# OGX360I-4CH_-_Main.net
KiCad netlist of a schematic drawn in EAGLE
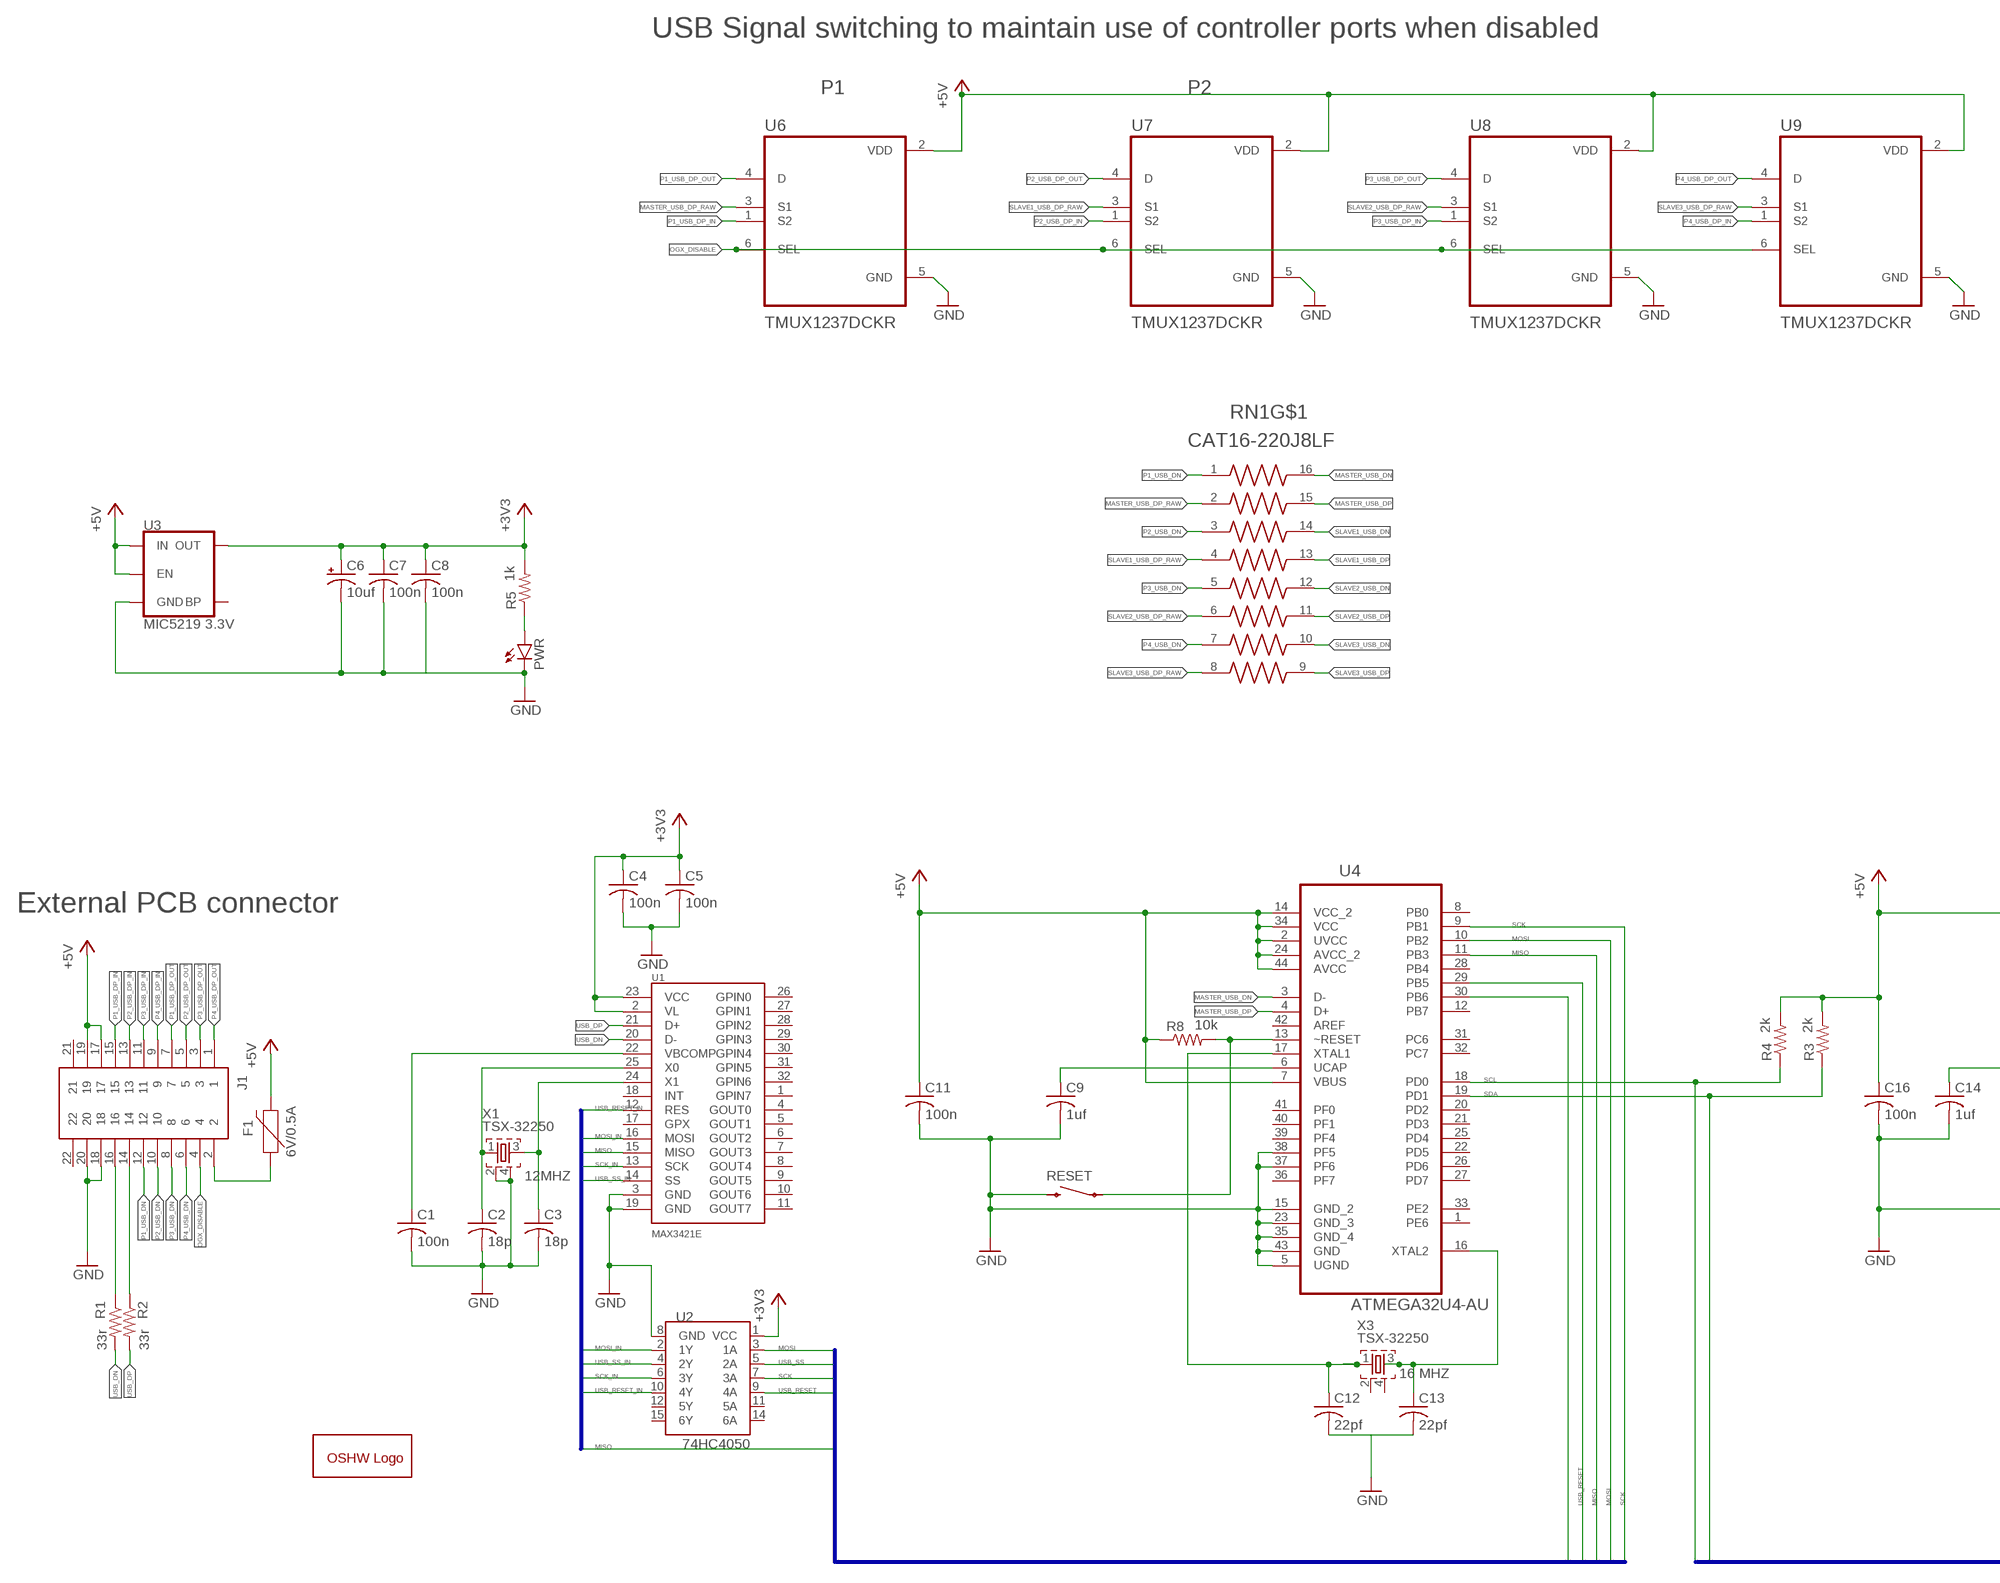
[diagram p0: schematic, sheet 1, part 1 of 2]
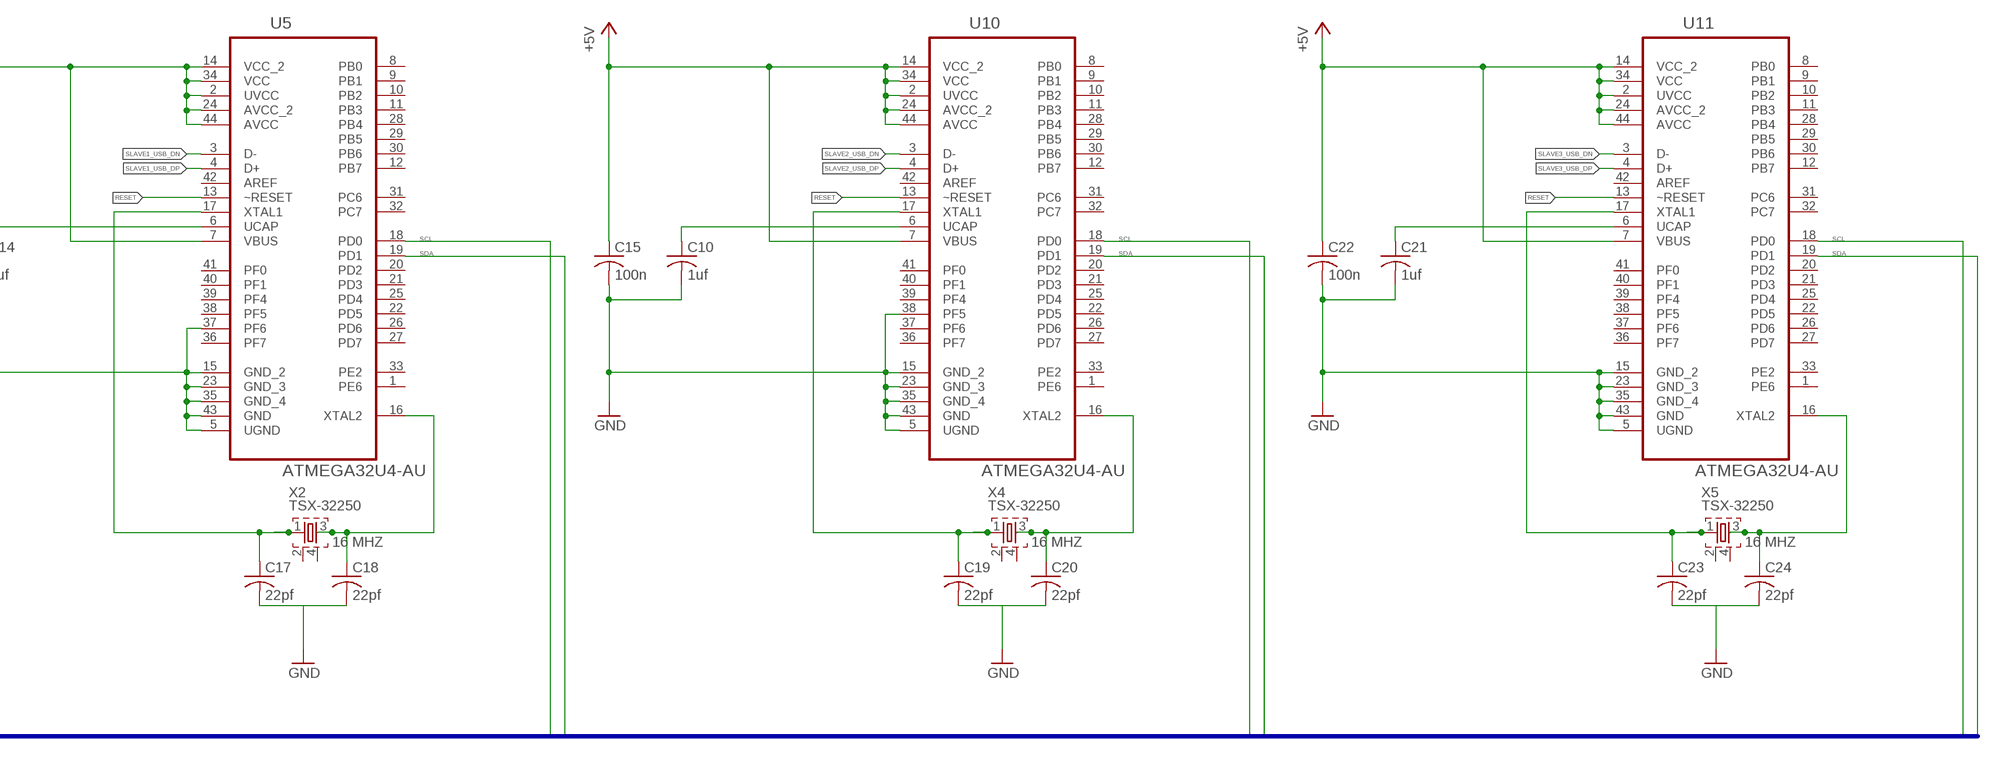
[diagram p1: schematic, sheet 1, part 2 of 2]

(export (version "E")
  (design (tool "Eeschema 10.0.6"))
  (components
    (comp (ref "C1")
      (value "100n")
      (footprint "eagle-import:C0805")
      (libsource (lib "eagle-import") (part "C-USC0805"))
    )
    (comp (ref "C2")
      (value "18p")
      (footprint "eagle-import:C0805")
      (libsource (lib "eagle-import") (part "C-USC0805"))
    )
    (comp (ref "C3")
      (value "18p")
      (footprint "eagle-import:C0805")
      (libsource (lib "eagle-import") (part "C-USC0805"))
    )
    (comp (ref "C4")
      (value "100n")
      (footprint "eagle-import:C0805")
      (libsource (lib "eagle-import") (part "C-USC0805"))
    )
    (comp (ref "C5")
      (value "100n")
      (footprint "eagle-import:C0805")
      (libsource (lib "eagle-import") (part "C-USC0805"))
    )
    (comp (ref "C6")
      (value "10uf")
      (footprint "eagle-import:153CLV-0405")
      (libsource (lib "eagle-import") (part "CPOL-US153CLV-0405"))
    )
    (comp (ref "C7")
      (value "100n")
      (footprint "eagle-import:C0805")
      (libsource (lib "eagle-import") (part "C-USC0805"))
    )
    (comp (ref "C8")
      (value "100n")
      (footprint "eagle-import:C0805")
      (libsource (lib "eagle-import") (part "C-USC0805"))
    )
    (comp (ref "C9")
      (value "1uf")
      (footprint "eagle-import:C0805")
      (libsource (lib "eagle-import") (part "C-USC0805"))
    )
    (comp (ref "C10")
      (value "1uf")
      (footprint "eagle-import:C0805")
      (libsource (lib "eagle-import") (part "C-USC0805"))
    )
    (comp (ref "C11")
      (value "100n")
      (footprint "eagle-import:C0805")
      (libsource (lib "eagle-import") (part "C-USC0805"))
    )
    (comp (ref "C12")
      (value "22pf")
      (footprint "eagle-import:C0805")
      (libsource (lib "eagle-import") (part "C-USC0805"))
    )
    (comp (ref "C13")
      (value "22pf")
      (footprint "eagle-import:C0805")
      (libsource (lib "eagle-import") (part "C-USC0805"))
    )
    (comp (ref "C14")
      (value "1uf")
      (footprint "eagle-import:C0805")
      (libsource (lib "eagle-import") (part "C-USC0805"))
    )
    (comp (ref "C15")
      (value "100n")
      (footprint "eagle-import:C0805")
      (libsource (lib "eagle-import") (part "C-USC0805"))
    )
    (comp (ref "C16")
      (value "100n")
      (footprint "eagle-import:C0805")
      (libsource (lib "eagle-import") (part "C-USC0805"))
    )
    (comp (ref "C17")
      (value "22pf")
      (footprint "eagle-import:C0805")
      (libsource (lib "eagle-import") (part "C-USC0805"))
    )
    (comp (ref "C18")
      (value "22pf")
      (footprint "eagle-import:C0805")
      (libsource (lib "eagle-import") (part "C-USC0805"))
    )
    (comp (ref "C19")
      (value "22pf")
      (footprint "eagle-import:C0805")
      (libsource (lib "eagle-import") (part "C-USC0805"))
    )
    (comp (ref "C20")
      (value "22pf")
      (footprint "eagle-import:C0805")
      (libsource (lib "eagle-import") (part "C-USC0805"))
    )
    (comp (ref "C21")
      (value "1uf")
      (footprint "eagle-import:C0805")
      (libsource (lib "eagle-import") (part "C-USC0805"))
    )
    (comp (ref "C22")
      (value "100n")
      (footprint "eagle-import:C0805")
      (libsource (lib "eagle-import") (part "C-USC0805"))
    )
    (comp (ref "C23")
      (value "22pf")
      (footprint "eagle-import:C0805")
      (libsource (lib "eagle-import") (part "C-USC0805"))
    )
    (comp (ref "C24")
      (value "22pf")
      (footprint "eagle-import:C0805")
      (libsource (lib "eagle-import") (part "C-USC0805"))
    )
    (comp (ref "F1")
      (value "6V/0.5A")
      (footprint "eagle-import:1206")
      (libsource (lib "eagle-import") (part "PPTC_HALF-AMP"))
    )
    (comp (ref "GOLD_ORB_SM1")
      (value "OSHWLOGOLOGO8MM")
      (footprint "eagle-import:OSHW_8MM")
      (libsource (lib "eagle-import") (part "OSHWLOGOLOGO8MM"))
    )
    (comp (ref "J1")
      (value "SM20B-SRDS-G-TF(LF)(SN)")
      (footprint "eagle-import:SM20BSRDSGTFLFSN")
      (libsource (lib "eagle-import") (part "SM20B-SRDS-G-TF(LF)(SN)"))
    )
    (comp (ref "PWR")
      (value "LEDCHIP-LED0805")
      (footprint "eagle-import:CHIP-LED0805")
      (libsource (lib "eagle-import") (part "LEDCHIP-LED0805"))
    )
    (comp (ref "R1")
      (value "33r")
      (footprint "eagle-import:M0805")
      (libsource (lib "eagle-import") (part "R-US_M0805"))
    )
    (comp (ref "R2")
      (value "33r")
      (footprint "eagle-import:M0805")
      (libsource (lib "eagle-import") (part "R-US_M0805"))
    )
    (comp (ref "R3")
      (value "2k")
      (footprint "eagle-import:M0805")
      (libsource (lib "eagle-import") (part "R-US_M0805"))
    )
    (comp (ref "R4")
      (value "2k")
      (footprint "eagle-import:M0805")
      (libsource (lib "eagle-import") (part "R-US_M0805"))
    )
    (comp (ref "R5")
      (value "1k")
      (footprint "eagle-import:M0805")
      (libsource (lib "eagle-import") (part "R-US_M0805"))
    )
    (comp (ref "R8")
      (value "10k")
      (footprint "eagle-import:M0805")
      (libsource (lib "eagle-import") (part "R-US_M0805"))
    )
    (comp (ref "RESET")
      (value "TL3305AF160QG")
      (footprint "eagle-import:TL3305AF160QG")
      (libsource (lib "eagle-import") (part "TL3305AF160QG"))
    )
    (comp (ref "RN1")
      (value "CAT16-220J8LF")
      (footprint "eagle-import:RESCAV80P640X160X75-16N")
      (fields (field (name "MF") "Bourns") (field (name "MP") "CAT16-330J8LF"))
      (libsource (lib "eagle-import") (part "CAT16-330J8LF"))
    )
    (comp (ref "U1")
      (value "MAX3421E")
      (footprint "eagle-import:TQFP32-5MM")
      (fields (field (name "MF") "Maxim Integrated"))
      (libsource (lib "eagle-import") (part "MAX3421E"))
    )
    (comp (ref "U2")
      (value "74HC4050")
      (footprint "eagle-import:SO16")
      (libsource (lib "eagle-import") (part "HEX_CONVERTER"))
    )
    (comp (ref "U3")
      (value "MIC5219 3.3V")
      (footprint "eagle-import:SOT23-5")
      (libsource (lib "eagle-import") (part "V_REG_MIC52193.3V"))
    )
    (comp (ref "U4")
      (value "ATMEGA32U4-AU")
      (footprint "eagle-import:QFP80P1200X1200X120-44N")
      (fields (field (name "MF") "Microchip"))
      (libsource (lib "eagle-import") (part "ATMEGA32U4-AU"))
    )
    (comp (ref "U5")
      (value "ATMEGA32U4-AU")
      (footprint "eagle-import:QFP80P1200X1200X120-44N")
      (fields (field (name "MF") "Microchip"))
      (libsource (lib "eagle-import") (part "ATMEGA32U4-AU"))
    )
    (comp (ref "U6")
      (value "TMUX1237DCKR")
      (footprint "eagle-import:SOT65P210X110-6N")
      (fields (field (name "MF") "Texas Instruments"))
      (libsource (lib "eagle-import") (part "TMUX1237DCKR"))
    )
    (comp (ref "U7")
      (value "TMUX1237DCKR")
      (footprint "eagle-import:SOT65P210X110-6N")
      (fields (field (name "MF") "Texas Instruments"))
      (libsource (lib "eagle-import") (part "TMUX1237DCKR"))
    )
    (comp (ref "U8")
      (value "TMUX1237DCKR")
      (footprint "eagle-import:SOT65P210X110-6N")
      (fields (field (name "MF") "Texas Instruments"))
      (libsource (lib "eagle-import") (part "TMUX1237DCKR"))
    )
    (comp (ref "U9")
      (value "TMUX1237DCKR")
      (footprint "eagle-import:SOT65P210X110-6N")
      (fields (field (name "MF") "Texas Instruments"))
      (libsource (lib "eagle-import") (part "TMUX1237DCKR"))
    )
    (comp (ref "U10")
      (value "ATMEGA32U4-AU")
      (footprint "eagle-import:QFP80P1200X1200X120-44N")
      (fields (field (name "MF") "Microchip"))
      (libsource (lib "eagle-import") (part "ATMEGA32U4-AU"))
    )
    (comp (ref "U11")
      (value "ATMEGA32U4-AU")
      (footprint "eagle-import:QFP80P1200X1200X120-44N")
      (fields (field (name "MF") "Microchip"))
      (libsource (lib "eagle-import") (part "ATMEGA32U4-AU"))
    )
    (comp (ref "X1")
      (value "TSX-32250")
      (footprint "eagle-import:TSX-3225")
      (fields
        (field (name "DIGI-KEY_PART_NUMBER") "SER4180CT-ND")
        (field (name "MF") "EPSON")
        (field (name "MP") "TSX-3225")
      )
      (libsource (lib "eagle-import") (part "TSX-32250"))
    )
    (comp (ref "X2")
      (value "TSX-32250")
      (footprint "eagle-import:TSX-3225")
      (fields
        (field (name "DIGI-KEY_PART_NUMBER") "SER4180CT-ND")
        (field (name "MF") "EPSON")
        (field (name "MP") "TSX-3225")
      )
      (libsource (lib "eagle-import") (part "TSX-32250"))
    )
    (comp (ref "X3")
      (value "TSX-32250")
      (footprint "eagle-import:TSX-3225")
      (fields
        (field (name "DIGI-KEY_PART_NUMBER") "SER4180CT-ND")
        (field (name "MF") "EPSON")
        (field (name "MP") "TSX-3225")
      )
      (libsource (lib "eagle-import") (part "TSX-32250"))
    )
    (comp (ref "X4")
      (value "TSX-32250")
      (footprint "eagle-import:TSX-3225")
      (fields
        (field (name "DIGI-KEY_PART_NUMBER") "SER4180CT-ND")
        (field (name "MF") "EPSON")
        (field (name "MP") "TSX-3225")
      )
      (libsource (lib "eagle-import") (part "TSX-32250"))
    )
    (comp (ref "X5")
      (value "TSX-32250")
      (footprint "eagle-import:TSX-3225")
      (fields
        (field (name "DIGI-KEY_PART_NUMBER") "SER4180CT-ND")
        (field (name "MF") "EPSON")
        (field (name "MP") "TSX-3225")
      )
      (libsource (lib "eagle-import") (part "TSX-32250"))
    )
  )
  (nets
    (net (code "1") (name "+3V3") (class "Default")
      (node (ref "C4") (pin "1") (pinfunction "1_1") (pintype "passive"))
      (node (ref "C5") (pin "1") (pinfunction "1_1") (pintype "passive"))
      (node (ref "C6") (pin "+") (pinfunction "+_+") (pintype "passive"))
      (node (ref "C7") (pin "1") (pinfunction "1_1") (pintype "passive"))
      (node (ref "C8") (pin "1") (pinfunction "1_1") (pintype "passive"))
      (node (ref "R5") (pin "2") (pinfunction "2_2") (pintype "passive"))
      (node (ref "U1") (pin "2") (pinfunction "VL_2") (pintype "bidirectional"))
      (node (ref "U1") (pin "23") (pinfunction "VCC_23") (pintype "bidirectional"))
      (node (ref "U2") (pin "1") (pinfunction "VCC_1") (pintype "bidirectional"))
      (node (ref "U3") (pin "5") (pinfunction "OUT_5") (pintype "passive"))
    )
    (net (code "2") (name "+5V") (class "Default")
      (node (ref "C11") (pin "1") (pinfunction "1_1") (pintype "passive"))
      (node (ref "C15") (pin "1") (pinfunction "1_1") (pintype "passive"))
      (node (ref "C16") (pin "1") (pinfunction "1_1") (pintype "passive"))
      (node (ref "C22") (pin "1") (pinfunction "1_1") (pintype "passive"))
      (node (ref "F1") (pin "2") (pinfunction "2_2") (pintype "bidirectional"))
      (node (ref "J1") (pin "17") (pinfunction "17_17") (pintype "bidirectional"))
      (node (ref "J1") (pin "19") (pinfunction "19_19") (pintype "bidirectional"))
      (node (ref "R3") (pin "2") (pinfunction "2_2") (pintype "passive"))
      (node (ref "R4") (pin "2") (pinfunction "2_2") (pintype "passive"))
      (node (ref "R8") (pin "1") (pinfunction "1_1") (pintype "passive"))
      (node (ref "U10") (pin "14") (pinfunction "VCC_2_14") (pintype "power_in"))
      (node (ref "U10") (pin "2") (pinfunction "UVCC_2") (pintype "power_in"))
      (node (ref "U10") (pin "24") (pinfunction "AVCC_2_24") (pintype "power_in"))
      (node (ref "U10") (pin "34") (pinfunction "VCC_34") (pintype "power_in"))
      (node (ref "U10") (pin "44") (pinfunction "AVCC_44") (pintype "power_in"))
      (node (ref "U10") (pin "7") (pinfunction "VBUS_7") (pintype "input"))
      (node (ref "U11") (pin "14") (pinfunction "VCC_2_14") (pintype "power_in"))
      (node (ref "U11") (pin "2") (pinfunction "UVCC_2") (pintype "power_in"))
      (node (ref "U11") (pin "24") (pinfunction "AVCC_2_24") (pintype "power_in"))
      (node (ref "U11") (pin "34") (pinfunction "VCC_34") (pintype "power_in"))
      (node (ref "U11") (pin "44") (pinfunction "AVCC_44") (pintype "power_in"))
      (node (ref "U11") (pin "7") (pinfunction "VBUS_7") (pintype "input"))
      (node (ref "U3") (pin "1") (pinfunction "IN_1") (pintype "input"))
      (node (ref "U3") (pin "3") (pinfunction "EN_3") (pintype "input"))
      (node (ref "U4") (pin "14") (pinfunction "VCC_2_14") (pintype "power_in"))
      (node (ref "U4") (pin "2") (pinfunction "UVCC_2") (pintype "power_in"))
      (node (ref "U4") (pin "24") (pinfunction "AVCC_2_24") (pintype "power_in"))
      (node (ref "U4") (pin "34") (pinfunction "VCC_34") (pintype "power_in"))
      (node (ref "U4") (pin "44") (pinfunction "AVCC_44") (pintype "power_in"))
      (node (ref "U4") (pin "7") (pinfunction "VBUS_7") (pintype "input"))
      (node (ref "U5") (pin "14") (pinfunction "VCC_2_14") (pintype "power_in"))
      (node (ref "U5") (pin "2") (pinfunction "UVCC_2") (pintype "power_in"))
      (node (ref "U5") (pin "24") (pinfunction "AVCC_2_24") (pintype "power_in"))
      (node (ref "U5") (pin "34") (pinfunction "VCC_34") (pintype "power_in"))
      (node (ref "U5") (pin "44") (pinfunction "AVCC_44") (pintype "power_in"))
      (node (ref "U5") (pin "7") (pinfunction "VBUS_7") (pintype "input"))
      (node (ref "U6") (pin "2") (pinfunction "VDD_2") (pintype "power_in"))
      (node (ref "U7") (pin "2") (pinfunction "VDD_2") (pintype "power_in"))
      (node (ref "U8") (pin "2") (pinfunction "VDD_2") (pintype "power_in"))
      (node (ref "U9") (pin "2") (pinfunction "VDD_2") (pintype "power_in"))
    )
    (net (code "3") (name "/MISO") (class "Default")
      (node (ref "U1") (pin "15") (pinfunction "MISO_15") (pintype "bidirectional"))
      (node (ref "U4") (pin "11") (pinfunction "PB3_11") (pintype "bidirectional"))
    )
    (net (code "4") (name "/MOSI") (class "Default")
      (node (ref "U2") (pin "3") (pinfunction "1A_3") (pintype "bidirectional"))
      (node (ref "U4") (pin "10") (pinfunction "PB2_10") (pintype "bidirectional"))
    )
    (net (code "5") (name "/MOSI_IN") (class "Default")
      (node (ref "U1") (pin "16") (pinfunction "MOSI_16") (pintype "bidirectional"))
      (node (ref "U2") (pin "2") (pinfunction "1Y_2") (pintype "bidirectional"))
    )
    (net (code "6") (name "/SCK") (class "Default")
      (node (ref "U2") (pin "7") (pinfunction "3A_7") (pintype "bidirectional"))
      (node (ref "U4") (pin "9") (pinfunction "PB1_9") (pintype "bidirectional"))
    )
    (net (code "7") (name "/SCK_IN") (class "Default")
      (node (ref "U1") (pin "13") (pinfunction "SCK_13") (pintype "bidirectional"))
      (node (ref "U2") (pin "6") (pinfunction "3Y_6") (pintype "bidirectional"))
    )
    (net (code "8") (name "/SCL") (class "Default")
      (node (ref "R4") (pin "1") (pinfunction "1_1") (pintype "passive"))
      (node (ref "U10") (pin "18") (pinfunction "PD0_18") (pintype "bidirectional"))
      (node (ref "U11") (pin "18") (pinfunction "PD0_18") (pintype "bidirectional"))
      (node (ref "U4") (pin "18") (pinfunction "PD0_18") (pintype "bidirectional"))
      (node (ref "U5") (pin "18") (pinfunction "PD0_18") (pintype "bidirectional"))
    )
    (net (code "9") (name "/SDA") (class "Default")
      (node (ref "R3") (pin "1") (pinfunction "1_1") (pintype "passive"))
      (node (ref "U10") (pin "19") (pinfunction "PD1_19") (pintype "bidirectional"))
      (node (ref "U11") (pin "19") (pinfunction "PD1_19") (pintype "bidirectional"))
      (node (ref "U4") (pin "19") (pinfunction "PD1_19") (pintype "bidirectional"))
      (node (ref "U5") (pin "19") (pinfunction "PD1_19") (pintype "bidirectional"))
    )
    (net (code "10") (name "/USB_RESET") (class "Default")
      (node (ref "U2") (pin "9") (pinfunction "4A_9") (pintype "bidirectional"))
      (node (ref "U4") (pin "29") (pinfunction "PB5_29") (pintype "bidirectional"))
    )
    (net (code "11") (name "/USB_RESET_IN") (class "Default")
      (node (ref "U1") (pin "12") (pinfunction "RES_12") (pintype "bidirectional"))
      (node (ref "U2") (pin "10") (pinfunction "4Y_10") (pintype "bidirectional"))
    )
    (net (code "12") (name "/USB_SS") (class "Default")
      (node (ref "U2") (pin "5") (pinfunction "2A_5") (pintype "bidirectional"))
      (node (ref "U4") (pin "30") (pinfunction "PB6_30") (pintype "bidirectional"))
    )
    (net (code "13") (name "/USB_SS_IN") (class "Default")
      (node (ref "U1") (pin "14") (pinfunction "SS_14") (pintype "bidirectional"))
      (node (ref "U2") (pin "4") (pinfunction "2Y_4") (pintype "bidirectional"))
    )
    (net (code "14") (name "GND") (class "Default")
      (node (ref "C1") (pin "2") (pinfunction "2_2") (pintype "passive"))
      (node (ref "C10") (pin "2") (pinfunction "2_2") (pintype "passive"))
      (node (ref "C11") (pin "2") (pinfunction "2_2") (pintype "passive"))
      (node (ref "C12") (pin "2") (pinfunction "2_2") (pintype "passive"))
      (node (ref "C13") (pin "2") (pinfunction "2_2") (pintype "passive"))
      (node (ref "C14") (pin "2") (pinfunction "2_2") (pintype "passive"))
      (node (ref "C15") (pin "2") (pinfunction "2_2") (pintype "passive"))
      (node (ref "C16") (pin "2") (pinfunction "2_2") (pintype "passive"))
      (node (ref "C17") (pin "2") (pinfunction "2_2") (pintype "passive"))
      (node (ref "C18") (pin "2") (pinfunction "2_2") (pintype "passive"))
      (node (ref "C19") (pin "2") (pinfunction "2_2") (pintype "passive"))
      (node (ref "C2") (pin "2") (pinfunction "2_2") (pintype "passive"))
      (node (ref "C20") (pin "2") (pinfunction "2_2") (pintype "passive"))
      (node (ref "C21") (pin "2") (pinfunction "2_2") (pintype "passive"))
      (node (ref "C22") (pin "2") (pinfunction "2_2") (pintype "passive"))
      (node (ref "C23") (pin "2") (pinfunction "2_2") (pintype "passive"))
      (node (ref "C24") (pin "2") (pinfunction "2_2") (pintype "passive"))
      (node (ref "C3") (pin "2") (pinfunction "2_2") (pintype "passive"))
      (node (ref "C4") (pin "2") (pinfunction "2_2") (pintype "passive"))
      (node (ref "C5") (pin "2") (pinfunction "2_2") (pintype "passive"))
      (node (ref "C6") (pin "-") (pinfunction "-_-") (pintype "passive"))
      (node (ref "C7") (pin "2") (pinfunction "2_2") (pintype "passive"))
      (node (ref "C8") (pin "2") (pinfunction "2_2") (pintype "passive"))
      (node (ref "C9") (pin "2") (pinfunction "2_2") (pintype "passive"))
      (node (ref "J1") (pin "18") (pinfunction "18_18") (pintype "bidirectional"))
      (node (ref "J1") (pin "20") (pinfunction "20_20") (pintype "bidirectional"))
      (node (ref "PWR") (pin "C") (pinfunction "C_C") (pintype "passive"))
      (node (ref "RESET") (pin "P$1") (pinfunction "P$1_P$1") (pintype "bidirectional"))
      (node (ref "RESET") (pin "P$2") (pinfunction "P$1_P$2") (pintype "bidirectional"))
      (node (ref "U1") (pin "19") (pinfunction "GND_19") (pintype "bidirectional"))
      (node (ref "U1") (pin "3") (pinfunction "GND_3") (pintype "bidirectional"))
      (node (ref "U10") (pin "15") (pinfunction "GND_2_15") (pintype "passive"))
      (node (ref "U10") (pin "23") (pinfunction "GND_3_23") (pintype "passive"))
      (node (ref "U10") (pin "35") (pinfunction "GND_4_35") (pintype "passive"))
      (node (ref "U10") (pin "38") (pinfunction "PF5_38") (pintype "bidirectional"))
      (node (ref "U10") (pin "43") (pinfunction "GND_43") (pintype "passive"))
      (node (ref "U10") (pin "5") (pinfunction "UGND_5") (pintype "passive"))
      (node (ref "U11") (pin "15") (pinfunction "GND_2_15") (pintype "passive"))
      (node (ref "U11") (pin "23") (pinfunction "GND_3_23") (pintype "passive"))
      (node (ref "U11") (pin "35") (pinfunction "GND_4_35") (pintype "passive"))
      (node (ref "U11") (pin "43") (pinfunction "GND_43") (pintype "passive"))
      (node (ref "U11") (pin "5") (pinfunction "UGND_5") (pintype "passive"))
      (node (ref "U2") (pin "8") (pinfunction "GND_8") (pintype "bidirectional"))
      (node (ref "U3") (pin "2") (pinfunction "GND_2") (pintype "input"))
      (node (ref "U4") (pin "15") (pinfunction "GND_2_15") (pintype "passive"))
      (node (ref "U4") (pin "23") (pinfunction "GND_3_23") (pintype "passive"))
      (node (ref "U4") (pin "35") (pinfunction "GND_4_35") (pintype "passive"))
      (node (ref "U4") (pin "37") (pinfunction "PF6_37") (pintype "bidirectional"))
      (node (ref "U4") (pin "38") (pinfunction "PF5_38") (pintype "bidirectional"))
      (node (ref "U4") (pin "43") (pinfunction "GND_43") (pintype "passive"))
      (node (ref "U4") (pin "5") (pinfunction "UGND_5") (pintype "passive"))
      (node (ref "U5") (pin "15") (pinfunction "GND_2_15") (pintype "passive"))
      (node (ref "U5") (pin "23") (pinfunction "GND_3_23") (pintype "passive"))
      (node (ref "U5") (pin "35") (pinfunction "GND_4_35") (pintype "passive"))
      (node (ref "U5") (pin "37") (pinfunction "PF6_37") (pintype "bidirectional"))
      (node (ref "U5") (pin "43") (pinfunction "GND_43") (pintype "passive"))
      (node (ref "U5") (pin "5") (pinfunction "UGND_5") (pintype "passive"))
      (node (ref "U6") (pin "5") (pinfunction "GND_5") (pintype "power_in"))
      (node (ref "U7") (pin "5") (pinfunction "GND_5") (pintype "power_in"))
      (node (ref "U8") (pin "5") (pinfunction "GND_5") (pintype "power_in"))
      (node (ref "U9") (pin "5") (pinfunction "GND_5") (pintype "power_in"))
      (node (ref "X1") (pin "2") (pinfunction "2_2") (pintype "passive"))
      (node (ref "X1") (pin "4") (pinfunction "4_4") (pintype "passive"))
    )
    (net (code "15") (name "MASTER_USB_DN") (class "Default")
      (node (ref "RN1") (pin "16") (pinfunction "R1-2_16") (pintype "passive"))
      (node (ref "U4") (pin "3") (pinfunction "D-_3") (pintype "passive"))
    )
    (net (code "16") (name "MASTER_USB_DP") (class "Default")
      (node (ref "RN1") (pin "15") (pinfunction "R2-2_15") (pintype "passive"))
      (node (ref "U4") (pin "4") (pinfunction "D+_4") (pintype "passive"))
    )
    (net (code "17") (name "MASTER_USB_DP_RAW") (class "Default")
      (node (ref "RN1") (pin "2") (pinfunction "R2-1_2") (pintype "passive"))
      (node (ref "U6") (pin "3") (pinfunction "S1_3") (pintype "bidirectional"))
    )
    (net (code "18") (name "Net-(F1-Pad1)") (class "Default")
      (node (ref "F1") (pin "1") (pinfunction "1_1") (pintype "bidirectional"))
      (node (ref "J1") (pin "2") (pinfunction "2_2") (pintype "bidirectional"))
    )
    (net (code "19") (name "Net-(J1-Pad14)") (class "Default")
      (node (ref "J1") (pin "14") (pinfunction "14_14") (pintype "bidirectional"))
      (node (ref "R2") (pin "1") (pinfunction "1_1") (pintype "passive"))
    )
    (net (code "20") (name "Net-(J1-Pad16)") (class "Default")
      (node (ref "J1") (pin "16") (pinfunction "16_16") (pintype "bidirectional"))
      (node (ref "R1") (pin "1") (pinfunction "1_1") (pintype "passive"))
    )
    (net (code "21") (name "Net-(PWR-PadA)") (class "Default")
      (node (ref "PWR") (pin "A") (pinfunction "A_A") (pintype "passive"))
      (node (ref "R5") (pin "1") (pinfunction "1_1") (pintype "passive"))
    )
    (net (code "22") (name "Net-(U1-VBCOMP)") (class "Default")
      (node (ref "C1") (pin "1") (pinfunction "1_1") (pintype "passive"))
      (node (ref "U1") (pin "22") (pinfunction "VBCOMP_22") (pintype "bidirectional"))
    )
    (net (code "23") (name "Net-(U1-X0)") (class "Default")
      (node (ref "C2") (pin "1") (pinfunction "1_1") (pintype "passive"))
      (node (ref "U1") (pin "25") (pinfunction "X0_25") (pintype "bidirectional"))
      (node (ref "X1") (pin "1") (pinfunction "1_1") (pintype "passive"))
    )
    (net (code "24") (name "Net-(U1-X1)") (class "Default")
      (node (ref "C3") (pin "1") (pinfunction "1_1") (pintype "passive"))
      (node (ref "U1") (pin "24") (pinfunction "X1_24") (pintype "bidirectional"))
      (node (ref "X1") (pin "3") (pinfunction "3_3") (pintype "passive"))
    )
    (net (code "25") (name "Net-(U4-UCAP)") (class "Default")
      (node (ref "C9") (pin "1") (pinfunction "1_1") (pintype "passive"))
      (node (ref "U4") (pin "6") (pinfunction "UCAP_6") (pintype "power_in"))
    )
    (net (code "26") (name "Net-(U4-XTAL1)") (class "Default")
      (node (ref "C12") (pin "1") (pinfunction "1_1") (pintype "passive"))
      (node (ref "U4") (pin "17") (pinfunction "XTAL1_17") (pintype "input"))
      (node (ref "X3") (pin "1") (pinfunction "1_1") (pintype "passive"))
    )
    (net (code "27") (name "Net-(U4-XTAL2)") (class "Default")
      (node (ref "C13") (pin "1") (pinfunction "1_1") (pintype "passive"))
      (node (ref "U4") (pin "16") (pinfunction "XTAL2_16") (pintype "output"))
      (node (ref "X3") (pin "3") (pinfunction "3_3") (pintype "passive"))
    )
    (net (code "28") (name "Net-(U5-UCAP)") (class "Default")
      (node (ref "C14") (pin "1") (pinfunction "1_1") (pintype "passive"))
      (node (ref "U5") (pin "6") (pinfunction "UCAP_6") (pintype "power_in"))
    )
    (net (code "29") (name "Net-(U5-XTAL1)") (class "Default")
      (node (ref "C17") (pin "1") (pinfunction "1_1") (pintype "passive"))
      (node (ref "U5") (pin "17") (pinfunction "XTAL1_17") (pintype "input"))
      (node (ref "X2") (pin "1") (pinfunction "1_1") (pintype "passive"))
    )
    (net (code "30") (name "Net-(U5-XTAL2)") (class "Default")
      (node (ref "C18") (pin "1") (pinfunction "1_1") (pintype "passive"))
      (node (ref "U5") (pin "16") (pinfunction "XTAL2_16") (pintype "output"))
      (node (ref "X2") (pin "3") (pinfunction "3_3") (pintype "passive"))
    )
    (net (code "31") (name "Net-(U10-UCAP)") (class "Default")
      (node (ref "C10") (pin "1") (pinfunction "1_1") (pintype "passive"))
      (node (ref "U10") (pin "6") (pinfunction "UCAP_6") (pintype "power_in"))
    )
    (net (code "32") (name "Net-(U10-XTAL1)") (class "Default")
      (node (ref "C19") (pin "1") (pinfunction "1_1") (pintype "passive"))
      (node (ref "U10") (pin "17") (pinfunction "XTAL1_17") (pintype "input"))
      (node (ref "X4") (pin "1") (pinfunction "1_1") (pintype "passive"))
    )
    (net (code "33") (name "Net-(U10-XTAL2)") (class "Default")
      (node (ref "C20") (pin "1") (pinfunction "1_1") (pintype "passive"))
      (node (ref "U10") (pin "16") (pinfunction "XTAL2_16") (pintype "output"))
      (node (ref "X4") (pin "3") (pinfunction "3_3") (pintype "passive"))
    )
    (net (code "34") (name "Net-(U11-UCAP)") (class "Default")
      (node (ref "C21") (pin "1") (pinfunction "1_1") (pintype "passive"))
      (node (ref "U11") (pin "6") (pinfunction "UCAP_6") (pintype "power_in"))
    )
    (net (code "35") (name "Net-(U11-XTAL1)") (class "Default")
      (node (ref "C23") (pin "1") (pinfunction "1_1") (pintype "passive"))
      (node (ref "U11") (pin "17") (pinfunction "XTAL1_17") (pintype "input"))
      (node (ref "X5") (pin "1") (pinfunction "1_1") (pintype "passive"))
    )
    (net (code "36") (name "Net-(U11-XTAL2)") (class "Default")
      (node (ref "C24") (pin "1") (pinfunction "1_1") (pintype "passive"))
      (node (ref "U11") (pin "16") (pinfunction "XTAL2_16") (pintype "output"))
      (node (ref "X5") (pin "3") (pinfunction "3_3") (pintype "passive"))
    )
    (net (code "37") (name "OGX_DISABLE") (class "Default")
      (node (ref "J1") (pin "4") (pinfunction "4_4") (pintype "bidirectional"))
      (node (ref "U6") (pin "6") (pinfunction "SEL_6") (pintype "bidirectional"))
      (node (ref "U7") (pin "6") (pinfunction "SEL_6") (pintype "bidirectional"))
      (node (ref "U8") (pin "6") (pinfunction "SEL_6") (pintype "bidirectional"))
      (node (ref "U9") (pin "6") (pinfunction "SEL_6") (pintype "bidirectional"))
    )
    (net (code "38") (name "P1_USB_DN") (class "Default")
      (node (ref "J1") (pin "12") (pinfunction "12_12") (pintype "bidirectional"))
      (node (ref "RN1") (pin "1") (pinfunction "R1-1_1") (pintype "passive"))
    )
    (net (code "39") (name "P1_USB_DP_IN") (class "Default")
      (node (ref "J1") (pin "15") (pinfunction "15_15") (pintype "bidirectional"))
      (node (ref "U6") (pin "1") (pinfunction "S2_1") (pintype "bidirectional"))
    )
    (net (code "40") (name "P1_USB_DP_OUT") (class "Default")
      (node (ref "J1") (pin "7") (pinfunction "7_7") (pintype "bidirectional"))
      (node (ref "U6") (pin "4") (pinfunction "D_4") (pintype "bidirectional"))
    )
    (net (code "41") (name "P2_USB_DN") (class "Default")
      (node (ref "J1") (pin "10") (pinfunction "10_10") (pintype "bidirectional"))
      (node (ref "RN1") (pin "3") (pinfunction "R3-1_3") (pintype "passive"))
    )
    (net (code "42") (name "P2_USB_DP_IN") (class "Default")
      (node (ref "J1") (pin "13") (pinfunction "13_13") (pintype "bidirectional"))
      (node (ref "U7") (pin "1") (pinfunction "S2_1") (pintype "bidirectional"))
    )
    (net (code "43") (name "P2_USB_DP_OUT") (class "Default")
      (node (ref "J1") (pin "5") (pinfunction "5_5") (pintype "bidirectional"))
      (node (ref "U7") (pin "4") (pinfunction "D_4") (pintype "bidirectional"))
    )
    (net (code "44") (name "P3_USB_DN") (class "Default")
      (node (ref "J1") (pin "8") (pinfunction "8_8") (pintype "bidirectional"))
      (node (ref "RN1") (pin "5") (pinfunction "R5-1_5") (pintype "passive"))
    )
    (net (code "45") (name "P3_USB_DP_IN") (class "Default")
      (node (ref "J1") (pin "11") (pinfunction "11_11") (pintype "bidirectional"))
      (node (ref "U8") (pin "1") (pinfunction "S2_1") (pintype "bidirectional"))
    )
    (net (code "46") (name "P3_USB_DP_OUT") (class "Default")
      (node (ref "J1") (pin "3") (pinfunction "3_3") (pintype "bidirectional"))
      (node (ref "U8") (pin "4") (pinfunction "D_4") (pintype "bidirectional"))
    )
    (net (code "47") (name "P4_USB_DN") (class "Default")
      (node (ref "J1") (pin "6") (pinfunction "6_6") (pintype "bidirectional"))
      (node (ref "RN1") (pin "7") (pinfunction "R7-1_7") (pintype "passive"))
    )
    (net (code "48") (name "P4_USB_DP_IN") (class "Default")
      (node (ref "J1") (pin "9") (pinfunction "9_9") (pintype "bidirectional"))
      (node (ref "U9") (pin "1") (pinfunction "S2_1") (pintype "bidirectional"))
    )
    (net (code "49") (name "P4_USB_DP_OUT") (class "Default")
      (node (ref "J1") (pin "1") (pinfunction "1_1") (pintype "bidirectional"))
      (node (ref "U9") (pin "4") (pinfunction "D_4") (pintype "bidirectional"))
    )
    (net (code "50") (name "RESET") (class "Default")
      (node (ref "R8") (pin "2") (pinfunction "2_2") (pintype "passive"))
      (node (ref "RESET") (pin "P$3") (pinfunction "2_P$3") (pintype "bidirectional"))
      (node (ref "RESET") (pin "P$4") (pinfunction "2_P$4") (pintype "bidirectional"))
      (node (ref "U10") (pin "13") (pinfunction "~{RESET}_13") (pintype "input"))
      (node (ref "U11") (pin "13") (pinfunction "~{RESET}_13") (pintype "input"))
      (node (ref "U4") (pin "13") (pinfunction "~{RESET}_13") (pintype "input"))
      (node (ref "U5") (pin "13") (pinfunction "~{RESET}_13") (pintype "input"))
    )
    (net (code "51") (name "SLAVE1_USB_DN") (class "Default")
      (node (ref "RN1") (pin "14") (pinfunction "R3-2_14") (pintype "passive"))
      (node (ref "U5") (pin "3") (pinfunction "D-_3") (pintype "passive"))
    )
    (net (code "52") (name "SLAVE1_USB_DP") (class "Default")
      (node (ref "RN1") (pin "13") (pinfunction "R4-2_13") (pintype "passive"))
      (node (ref "U5") (pin "4") (pinfunction "D+_4") (pintype "passive"))
    )
    (net (code "53") (name "SLAVE1_USB_DP_RAW") (class "Default")
      (node (ref "RN1") (pin "4") (pinfunction "R4-1_4") (pintype "passive"))
      (node (ref "U7") (pin "3") (pinfunction "S1_3") (pintype "bidirectional"))
    )
    (net (code "54") (name "SLAVE2_USB_DN") (class "Default")
      (node (ref "RN1") (pin "12") (pinfunction "R5-2_12") (pintype "passive"))
      (node (ref "U10") (pin "3") (pinfunction "D-_3") (pintype "passive"))
    )
    (net (code "55") (name "SLAVE2_USB_DP") (class "Default")
      (node (ref "RN1") (pin "11") (pinfunction "R6-2_11") (pintype "passive"))
      (node (ref "U10") (pin "4") (pinfunction "D+_4") (pintype "passive"))
    )
    (net (code "56") (name "SLAVE2_USB_DP_RAW") (class "Default")
      (node (ref "RN1") (pin "6") (pinfunction "R6-1_6") (pintype "passive"))
      (node (ref "U8") (pin "3") (pinfunction "S1_3") (pintype "bidirectional"))
    )
    (net (code "57") (name "SLAVE3_USB_DN") (class "Default")
      (node (ref "RN1") (pin "10") (pinfunction "R7-2_10") (pintype "passive"))
      (node (ref "U11") (pin "3") (pinfunction "D-_3") (pintype "passive"))
    )
    (net (code "58") (name "SLAVE3_USB_DP") (class "Default")
      (node (ref "RN1") (pin "9") (pinfunction "R8-2_9") (pintype "passive"))
      (node (ref "U11") (pin "4") (pinfunction "D+_4") (pintype "passive"))
    )
    (net (code "59") (name "SLAVE3_USB_DP_RAW") (class "Default")
      (node (ref "RN1") (pin "8") (pinfunction "R8-1_8") (pintype "passive"))
      (node (ref "U9") (pin "3") (pinfunction "S1_3") (pintype "bidirectional"))
    )
    (net (code "60") (name "USB_DN") (class "Default")
      (node (ref "R1") (pin "2") (pinfunction "2_2") (pintype "passive"))
      (node (ref "U1") (pin "20") (pinfunction "D-_20") (pintype "bidirectional"))
    )
    (net (code "61") (name "USB_DP") (class "Default")
      (node (ref "R2") (pin "2") (pinfunction "2_2") (pintype "passive"))
      (node (ref "U1") (pin "21") (pinfunction "D+_21") (pintype "bidirectional"))
    )
    (net (code "62") (name "unconnected-(J1-Pad21)") (class "Default")
      (node (ref "J1") (pin "21") (pinfunction "21_21") (pintype "bidirectional"))
    )
    (net (code "63") (name "unconnected-(J1-Pad22)") (class "Default")
      (node (ref "J1") (pin "22") (pinfunction "22_22") (pintype "bidirectional"))
    )
    (net (code "64") (name "unconnected-(U1-GOUT0-Pad4)") (class "Default")
      (node (ref "U1") (pin "4") (pinfunction "GOUT0_4") (pintype "bidirectional"))
    )
    (net (code "65") (name "unconnected-(U1-GOUT1-Pad5)") (class "Default")
      (node (ref "U1") (pin "5") (pinfunction "GOUT1_5") (pintype "bidirectional"))
    )
    (net (code "66") (name "unconnected-(U1-GOUT2-Pad6)") (class "Default")
      (node (ref "U1") (pin "6") (pinfunction "GOUT2_6") (pintype "bidirectional"))
    )
    (net (code "67") (name "unconnected-(U1-GOUT3-Pad7)") (class "Default")
      (node (ref "U1") (pin "7") (pinfunction "GOUT3_7") (pintype "bidirectional"))
    )
    (net (code "68") (name "unconnected-(U1-GOUT4-Pad8)") (class "Default")
      (node (ref "U1") (pin "8") (pinfunction "GOUT4_8") (pintype "bidirectional"))
    )
    (net (code "69") (name "unconnected-(U1-GOUT5-Pad9)") (class "Default")
      (node (ref "U1") (pin "9") (pinfunction "GOUT5_9") (pintype "bidirectional"))
    )
    (net (code "70") (name "unconnected-(U1-GOUT6-Pad10)") (class "Default")
      (node (ref "U1") (pin "10") (pinfunction "GOUT6_10") (pintype "bidirectional"))
    )
    (net (code "71") (name "unconnected-(U1-GOUT7-Pad11)") (class "Default")
      (node (ref "U1") (pin "11") (pinfunction "GOUT7_11") (pintype "bidirectional"))
    )
    (net (code "72") (name "unconnected-(U1-GPIN0-Pad26)") (class "Default")
      (node (ref "U1") (pin "26") (pinfunction "GPIN0_26") (pintype "bidirectional"))
    )
    (net (code "73") (name "unconnected-(U1-GPIN1-Pad27)") (class "Default")
      (node (ref "U1") (pin "27") (pinfunction "GPIN1_27") (pintype "bidirectional"))
    )
    (net (code "74") (name "unconnected-(U1-GPIN2-Pad28)") (class "Default")
      (node (ref "U1") (pin "28") (pinfunction "GPIN2_28") (pintype "bidirectional"))
    )
    (net (code "75") (name "unconnected-(U1-GPIN3-Pad29)") (class "Default")
      (node (ref "U1") (pin "29") (pinfunction "GPIN3_29") (pintype "bidirectional"))
    )
    (net (code "76") (name "unconnected-(U1-GPIN4-Pad30)") (class "Default")
      (node (ref "U1") (pin "30") (pinfunction "GPIN4_30") (pintype "bidirectional"))
    )
    (net (code "77") (name "unconnected-(U1-GPIN5-Pad31)") (class "Default")
      (node (ref "U1") (pin "31") (pinfunction "GPIN5_31") (pintype "bidirectional"))
    )
    (net (code "78") (name "unconnected-(U1-GPIN6-Pad32)") (class "Default")
      (node (ref "U1") (pin "32") (pinfunction "GPIN6_32") (pintype "bidirectional"))
    )
    (net (code "79") (name "unconnected-(U1-GPIN7-Pad1)") (class "Default")
      (node (ref "U1") (pin "1") (pinfunction "GPIN7_1") (pintype "bidirectional"))
    )
    (net (code "80") (name "unconnected-(U1-GPX-Pad17)") (class "Default")
      (node (ref "U1") (pin "17") (pinfunction "GPX_17") (pintype "bidirectional"))
    )
    (net (code "81") (name "unconnected-(U1-INT-Pad18)") (class "Default")
      (node (ref "U1") (pin "18") (pinfunction "INT_18") (pintype "bidirectional"))
    )
    (net (code "82") (name "unconnected-(U2-5A-Pad11)") (class "Default")
      (node (ref "U2") (pin "11") (pinfunction "5A_11") (pintype "bidirectional"))
    )
    (net (code "83") (name "unconnected-(U2-5Y-Pad12)") (class "Default")
      (node (ref "U2") (pin "12") (pinfunction "5Y_12") (pintype "bidirectional"))
    )
    (net (code "84") (name "unconnected-(U2-6A-Pad14)") (class "Default")
      (node (ref "U2") (pin "14") (pinfunction "6A_14") (pintype "bidirectional"))
    )
    (net (code "85") (name "unconnected-(U2-6Y-Pad15)") (class "Default")
      (node (ref "U2") (pin "15") (pinfunction "6Y_15") (pintype "bidirectional"))
    )
    (net (code "86") (name "unconnected-(U3-BP-Pad4)") (class "Default")
      (node (ref "U3") (pin "4") (pinfunction "BP_4") (pintype "input"))
    )
    (net (code "87") (name "unconnected-(U4-AREF-Pad42)") (class "Default")
      (node (ref "U4") (pin "42") (pinfunction "AREF_42") (pintype "input"))
    )
    (net (code "88") (name "unconnected-(U4-PB0-Pad8)") (class "Default")
      (node (ref "U4") (pin "8") (pinfunction "PB0_8") (pintype "bidirectional"))
    )
    (net (code "89") (name "unconnected-(U4-PB4-Pad28)") (class "Default")
      (node (ref "U4") (pin "28") (pinfunction "PB4_28") (pintype "bidirectional"))
    )
    (net (code "90") (name "unconnected-(U4-PB7-Pad12)") (class "Default")
      (node (ref "U4") (pin "12") (pinfunction "PB7_12") (pintype "bidirectional"))
    )
    (net (code "91") (name "unconnected-(U4-PC6-Pad31)") (class "Default")
      (node (ref "U4") (pin "31") (pinfunction "PC6_31") (pintype "bidirectional"))
    )
    (net (code "92") (name "unconnected-(U4-PC7-Pad32)") (class "Default")
      (node (ref "U4") (pin "32") (pinfunction "PC7_32") (pintype "bidirectional"))
    )
    (net (code "93") (name "unconnected-(U4-PD2-Pad20)") (class "Default")
      (node (ref "U4") (pin "20") (pinfunction "PD2_20") (pintype "bidirectional"))
    )
    (net (code "94") (name "unconnected-(U4-PD3-Pad21)") (class "Default")
      (node (ref "U4") (pin "21") (pinfunction "PD3_21") (pintype "bidirectional"))
    )
    (net (code "95") (name "unconnected-(U4-PD4-Pad25)") (class "Default")
      (node (ref "U4") (pin "25") (pinfunction "PD4_25") (pintype "bidirectional"))
    )
    (net (code "96") (name "unconnected-(U4-PD5-Pad22)") (class "Default")
      (node (ref "U4") (pin "22") (pinfunction "PD5_22") (pintype "bidirectional"))
    )
    (net (code "97") (name "unconnected-(U4-PD6-Pad26)") (class "Default")
      (node (ref "U4") (pin "26") (pinfunction "PD6_26") (pintype "bidirectional"))
    )
    (net (code "98") (name "unconnected-(U4-PD7-Pad27)") (class "Default")
      (node (ref "U4") (pin "27") (pinfunction "PD7_27") (pintype "bidirectional"))
    )
    (net (code "99") (name "unconnected-(U4-PE2-Pad33)") (class "Default")
      (node (ref "U4") (pin "33") (pinfunction "PE2_33") (pintype "bidirectional"))
    )
    (net (code "100") (name "unconnected-(U4-PE6-Pad1)") (class "Default")
      (node (ref "U4") (pin "1") (pinfunction "PE6_1") (pintype "bidirectional"))
    )
    (net (code "101") (name "unconnected-(U4-PF0-Pad41)") (class "Default")
      (node (ref "U4") (pin "41") (pinfunction "PF0_41") (pintype "bidirectional"))
    )
    (net (code "102") (name "unconnected-(U4-PF1-Pad40)") (class "Default")
      (node (ref "U4") (pin "40") (pinfunction "PF1_40") (pintype "bidirectional"))
    )
    (net (code "103") (name "unconnected-(U4-PF4-Pad39)") (class "Default")
      (node (ref "U4") (pin "39") (pinfunction "PF4_39") (pintype "bidirectional"))
    )
    (net (code "104") (name "unconnected-(U4-PF7-Pad36)") (class "Default")
      (node (ref "U4") (pin "36") (pinfunction "PF7_36") (pintype "bidirectional"))
    )
    (net (code "105") (name "unconnected-(U5-AREF-Pad42)") (class "Default")
      (node (ref "U5") (pin "42") (pinfunction "AREF_42") (pintype "input"))
    )
    (net (code "106") (name "unconnected-(U5-PB0-Pad8)") (class "Default")
      (node (ref "U5") (pin "8") (pinfunction "PB0_8") (pintype "bidirectional"))
    )
    (net (code "107") (name "unconnected-(U5-PB1-Pad9)") (class "Default")
      (node (ref "U5") (pin "9") (pinfunction "PB1_9") (pintype "bidirectional"))
    )
    (net (code "108") (name "unconnected-(U5-PB2-Pad10)") (class "Default")
      (node (ref "U5") (pin "10") (pinfunction "PB2_10") (pintype "bidirectional"))
    )
    (net (code "109") (name "unconnected-(U5-PB3-Pad11)") (class "Default")
      (node (ref "U5") (pin "11") (pinfunction "PB3_11") (pintype "bidirectional"))
    )
    (net (code "110") (name "unconnected-(U5-PB4-Pad28)") (class "Default")
      (node (ref "U5") (pin "28") (pinfunction "PB4_28") (pintype "bidirectional"))
    )
    (net (code "111") (name "unconnected-(U5-PB5-Pad29)") (class "Default")
      (node (ref "U5") (pin "29") (pinfunction "PB5_29") (pintype "bidirectional"))
    )
    (net (code "112") (name "unconnected-(U5-PB6-Pad30)") (class "Default")
      (node (ref "U5") (pin "30") (pinfunction "PB6_30") (pintype "bidirectional"))
    )
    (net (code "113") (name "unconnected-(U5-PB7-Pad12)") (class "Default")
      (node (ref "U5") (pin "12") (pinfunction "PB7_12") (pintype "bidirectional"))
    )
    (net (code "114") (name "unconnected-(U5-PC6-Pad31)") (class "Default")
      (node (ref "U5") (pin "31") (pinfunction "PC6_31") (pintype "bidirectional"))
    )
    (net (code "115") (name "unconnected-(U5-PC7-Pad32)") (class "Default")
      (node (ref "U5") (pin "32") (pinfunction "PC7_32") (pintype "bidirectional"))
    )
    (net (code "116") (name "unconnected-(U5-PD2-Pad20)") (class "Default")
      (node (ref "U5") (pin "20") (pinfunction "PD2_20") (pintype "bidirectional"))
    )
    (net (code "117") (name "unconnected-(U5-PD3-Pad21)") (class "Default")
      (node (ref "U5") (pin "21") (pinfunction "PD3_21") (pintype "bidirectional"))
    )
    (net (code "118") (name "unconnected-(U5-PD4-Pad25)") (class "Default")
      (node (ref "U5") (pin "25") (pinfunction "PD4_25") (pintype "bidirectional"))
    )
    (net (code "119") (name "unconnected-(U5-PD5-Pad22)") (class "Default")
      (node (ref "U5") (pin "22") (pinfunction "PD5_22") (pintype "bidirectional"))
    )
    (net (code "120") (name "unconnected-(U5-PD6-Pad26)") (class "Default")
      (node (ref "U5") (pin "26") (pinfunction "PD6_26") (pintype "bidirectional"))
    )
    (net (code "121") (name "unconnected-(U5-PD7-Pad27)") (class "Default")
      (node (ref "U5") (pin "27") (pinfunction "PD7_27") (pintype "bidirectional"))
    )
    (net (code "122") (name "unconnected-(U5-PE2-Pad33)") (class "Default")
      (node (ref "U5") (pin "33") (pinfunction "PE2_33") (pintype "bidirectional"))
    )
    (net (code "123") (name "unconnected-(U5-PE6-Pad1)") (class "Default")
      (node (ref "U5") (pin "1") (pinfunction "PE6_1") (pintype "bidirectional"))
    )
    (net (code "124") (name "unconnected-(U5-PF0-Pad41)") (class "Default")
      (node (ref "U5") (pin "41") (pinfunction "PF0_41") (pintype "bidirectional"))
    )
    (net (code "125") (name "unconnected-(U5-PF1-Pad40)") (class "Default")
      (node (ref "U5") (pin "40") (pinfunction "PF1_40") (pintype "bidirectional"))
    )
    (net (code "126") (name "unconnected-(U5-PF4-Pad39)") (class "Default")
      (node (ref "U5") (pin "39") (pinfunction "PF4_39") (pintype "bidirectional"))
    )
    (net (code "127") (name "unconnected-(U5-PF5-Pad38)") (class "Default")
      (node (ref "U5") (pin "38") (pinfunction "PF5_38") (pintype "bidirectional"))
    )
    (net (code "128") (name "unconnected-(U5-PF7-Pad36)") (class "Default")
      (node (ref "U5") (pin "36") (pinfunction "PF7_36") (pintype "bidirectional"))
    )
    (net (code "129") (name "unconnected-(U10-AREF-Pad42)") (class "Default")
      (node (ref "U10") (pin "42") (pinfunction "AREF_42") (pintype "input"))
    )
    (net (code "130") (name "unconnected-(U10-PB0-Pad8)") (class "Default")
      (node (ref "U10") (pin "8") (pinfunction "PB0_8") (pintype "bidirectional"))
    )
    (net (code "131") (name "unconnected-(U10-PB1-Pad9)") (class "Default")
      (node (ref "U10") (pin "9") (pinfunction "PB1_9") (pintype "bidirectional"))
    )
    (net (code "132") (name "unconnected-(U10-PB2-Pad10)") (class "Default")
      (node (ref "U10") (pin "10") (pinfunction "PB2_10") (pintype "bidirectional"))
    )
    (net (code "133") (name "unconnected-(U10-PB3-Pad11)") (class "Default")
      (node (ref "U10") (pin "11") (pinfunction "PB3_11") (pintype "bidirectional"))
    )
    (net (code "134") (name "unconnected-(U10-PB4-Pad28)") (class "Default")
      (node (ref "U10") (pin "28") (pinfunction "PB4_28") (pintype "bidirectional"))
    )
    (net (code "135") (name "unconnected-(U10-PB5-Pad29)") (class "Default")
      (node (ref "U10") (pin "29") (pinfunction "PB5_29") (pintype "bidirectional"))
    )
    (net (code "136") (name "unconnected-(U10-PB6-Pad30)") (class "Default")
      (node (ref "U10") (pin "30") (pinfunction "PB6_30") (pintype "bidirectional"))
    )
    (net (code "137") (name "unconnected-(U10-PB7-Pad12)") (class "Default")
      (node (ref "U10") (pin "12") (pinfunction "PB7_12") (pintype "bidirectional"))
    )
    (net (code "138") (name "unconnected-(U10-PC6-Pad31)") (class "Default")
      (node (ref "U10") (pin "31") (pinfunction "PC6_31") (pintype "bidirectional"))
    )
    (net (code "139") (name "unconnected-(U10-PC7-Pad32)") (class "Default")
      (node (ref "U10") (pin "32") (pinfunction "PC7_32") (pintype "bidirectional"))
    )
    (net (code "140") (name "unconnected-(U10-PD2-Pad20)") (class "Default")
      (node (ref "U10") (pin "20") (pinfunction "PD2_20") (pintype "bidirectional"))
    )
    (net (code "141") (name "unconnected-(U10-PD3-Pad21)") (class "Default")
      (node (ref "U10") (pin "21") (pinfunction "PD3_21") (pintype "bidirectional"))
    )
    (net (code "142") (name "unconnected-(U10-PD4-Pad25)") (class "Default")
      (node (ref "U10") (pin "25") (pinfunction "PD4_25") (pintype "bidirectional"))
    )
    (net (code "143") (name "unconnected-(U10-PD5-Pad22)") (class "Default")
      (node (ref "U10") (pin "22") (pinfunction "PD5_22") (pintype "bidirectional"))
    )
    (net (code "144") (name "unconnected-(U10-PD6-Pad26)") (class "Default")
      (node (ref "U10") (pin "26") (pinfunction "PD6_26") (pintype "bidirectional"))
    )
    (net (code "145") (name "unconnected-(U10-PD7-Pad27)") (class "Default")
      (node (ref "U10") (pin "27") (pinfunction "PD7_27") (pintype "bidirectional"))
    )
    (net (code "146") (name "unconnected-(U10-PE2-Pad33)") (class "Default")
      (node (ref "U10") (pin "33") (pinfunction "PE2_33") (pintype "bidirectional"))
    )
    (net (code "147") (name "unconnected-(U10-PE6-Pad1)") (class "Default")
      (node (ref "U10") (pin "1") (pinfunction "PE6_1") (pintype "bidirectional"))
    )
    (net (code "148") (name "unconnected-(U10-PF0-Pad41)") (class "Default")
      (node (ref "U10") (pin "41") (pinfunction "PF0_41") (pintype "bidirectional"))
    )
    (net (code "149") (name "unconnected-(U10-PF1-Pad40)") (class "Default")
      (node (ref "U10") (pin "40") (pinfunction "PF1_40") (pintype "bidirectional"))
    )
    (net (code "150") (name "unconnected-(U10-PF4-Pad39)") (class "Default")
      (node (ref "U10") (pin "39") (pinfunction "PF4_39") (pintype "bidirectional"))
    )
    (net (code "151") (name "unconnected-(U10-PF6-Pad37)") (class "Default")
      (node (ref "U10") (pin "37") (pinfunction "PF6_37") (pintype "bidirectional"))
    )
    (net (code "152") (name "unconnected-(U10-PF7-Pad36)") (class "Default")
      (node (ref "U10") (pin "36") (pinfunction "PF7_36") (pintype "bidirectional"))
    )
    (net (code "153") (name "unconnected-(U11-AREF-Pad42)") (class "Default")
      (node (ref "U11") (pin "42") (pinfunction "AREF_42") (pintype "input"))
    )
    (net (code "154") (name "unconnected-(U11-PB0-Pad8)") (class "Default")
      (node (ref "U11") (pin "8") (pinfunction "PB0_8") (pintype "bidirectional"))
    )
    (net (code "155") (name "unconnected-(U11-PB1-Pad9)") (class "Default")
      (node (ref "U11") (pin "9") (pinfunction "PB1_9") (pintype "bidirectional"))
    )
    (net (code "156") (name "unconnected-(U11-PB2-Pad10)") (class "Default")
      (node (ref "U11") (pin "10") (pinfunction "PB2_10") (pintype "bidirectional"))
    )
    (net (code "157") (name "unconnected-(U11-PB3-Pad11)") (class "Default")
      (node (ref "U11") (pin "11") (pinfunction "PB3_11") (pintype "bidirectional"))
    )
    (net (code "158") (name "unconnected-(U11-PB4-Pad28)") (class "Default")
      (node (ref "U11") (pin "28") (pinfunction "PB4_28") (pintype "bidirectional"))
    )
    (net (code "159") (name "unconnected-(U11-PB5-Pad29)") (class "Default")
      (node (ref "U11") (pin "29") (pinfunction "PB5_29") (pintype "bidirectional"))
    )
    (net (code "160") (name "unconnected-(U11-PB6-Pad30)") (class "Default")
      (node (ref "U11") (pin "30") (pinfunction "PB6_30") (pintype "bidirectional"))
    )
    (net (code "161") (name "unconnected-(U11-PB7-Pad12)") (class "Default")
      (node (ref "U11") (pin "12") (pinfunction "PB7_12") (pintype "bidirectional"))
    )
    (net (code "162") (name "unconnected-(U11-PC6-Pad31)") (class "Default")
      (node (ref "U11") (pin "31") (pinfunction "PC6_31") (pintype "bidirectional"))
    )
    (net (code "163") (name "unconnected-(U11-PC7-Pad32)") (class "Default")
      (node (ref "U11") (pin "32") (pinfunction "PC7_32") (pintype "bidirectional"))
    )
    (net (code "164") (name "unconnected-(U11-PD2-Pad20)") (class "Default")
      (node (ref "U11") (pin "20") (pinfunction "PD2_20") (pintype "bidirectional"))
    )
    (net (code "165") (name "unconnected-(U11-PD3-Pad21)") (class "Default")
      (node (ref "U11") (pin "21") (pinfunction "PD3_21") (pintype "bidirectional"))
    )
    (net (code "166") (name "unconnected-(U11-PD4-Pad25)") (class "Default")
      (node (ref "U11") (pin "25") (pinfunction "PD4_25") (pintype "bidirectional"))
    )
    (net (code "167") (name "unconnected-(U11-PD5-Pad22)") (class "Default")
      (node (ref "U11") (pin "22") (pinfunction "PD5_22") (pintype "bidirectional"))
    )
    (net (code "168") (name "unconnected-(U11-PD6-Pad26)") (class "Default")
      (node (ref "U11") (pin "26") (pinfunction "PD6_26") (pintype "bidirectional"))
    )
    (net (code "169") (name "unconnected-(U11-PD7-Pad27)") (class "Default")
      (node (ref "U11") (pin "27") (pinfunction "PD7_27") (pintype "bidirectional"))
    )
    (net (code "170") (name "unconnected-(U11-PE2-Pad33)") (class "Default")
      (node (ref "U11") (pin "33") (pinfunction "PE2_33") (pintype "bidirectional"))
    )
    (net (code "171") (name "unconnected-(U11-PE6-Pad1)") (class "Default")
      (node (ref "U11") (pin "1") (pinfunction "PE6_1") (pintype "bidirectional"))
    )
    (net (code "172") (name "unconnected-(U11-PF0-Pad41)") (class "Default")
      (node (ref "U11") (pin "41") (pinfunction "PF0_41") (pintype "bidirectional"))
    )
    (net (code "173") (name "unconnected-(U11-PF1-Pad40)") (class "Default")
      (node (ref "U11") (pin "40") (pinfunction "PF1_40") (pintype "bidirectional"))
    )
    (net (code "174") (name "unconnected-(U11-PF4-Pad39)") (class "Default")
      (node (ref "U11") (pin "39") (pinfunction "PF4_39") (pintype "bidirectional"))
    )
    (net (code "175") (name "unconnected-(U11-PF5-Pad38)") (class "Default")
      (node (ref "U11") (pin "38") (pinfunction "PF5_38") (pintype "bidirectional"))
    )
    (net (code "176") (name "unconnected-(U11-PF6-Pad37)") (class "Default")
      (node (ref "U11") (pin "37") (pinfunction "PF6_37") (pintype "bidirectional"))
    )
    (net (code "177") (name "unconnected-(U11-PF7-Pad36)") (class "Default")
      (node (ref "U11") (pin "36") (pinfunction "PF7_36") (pintype "bidirectional"))
    )
    (net (code "178") (name "unconnected-(X2-Pad2)") (class "Default")
      (node (ref "X2") (pin "2") (pinfunction "2_2") (pintype "passive"))
    )
    (net (code "179") (name "unconnected-(X2-Pad4)") (class "Default")
      (node (ref "X2") (pin "4") (pinfunction "4_4") (pintype "passive"))
    )
    (net (code "180") (name "unconnected-(X3-Pad2)") (class "Default")
      (node (ref "X3") (pin "2") (pinfunction "2_2") (pintype "passive"))
    )
    (net (code "181") (name "unconnected-(X3-Pad4)") (class "Default")
      (node (ref "X3") (pin "4") (pinfunction "4_4") (pintype "passive"))
    )
    (net (code "182") (name "unconnected-(X4-Pad2)") (class "Default")
      (node (ref "X4") (pin "2") (pinfunction "2_2") (pintype "passive"))
    )
    (net (code "183") (name "unconnected-(X4-Pad4)") (class "Default")
      (node (ref "X4") (pin "4") (pinfunction "4_4") (pintype "passive"))
    )
    (net (code "184") (name "unconnected-(X5-Pad2)") (class "Default")
      (node (ref "X5") (pin "2") (pinfunction "2_2") (pintype "passive"))
    )
    (net (code "185") (name "unconnected-(X5-Pad4)") (class "Default")
      (node (ref "X5") (pin "4") (pinfunction "4_4") (pintype "passive"))
    )
  )
)
